# filters_no_gnd_vias.net
KiCad netlist of a schematic drawn in EAGLE
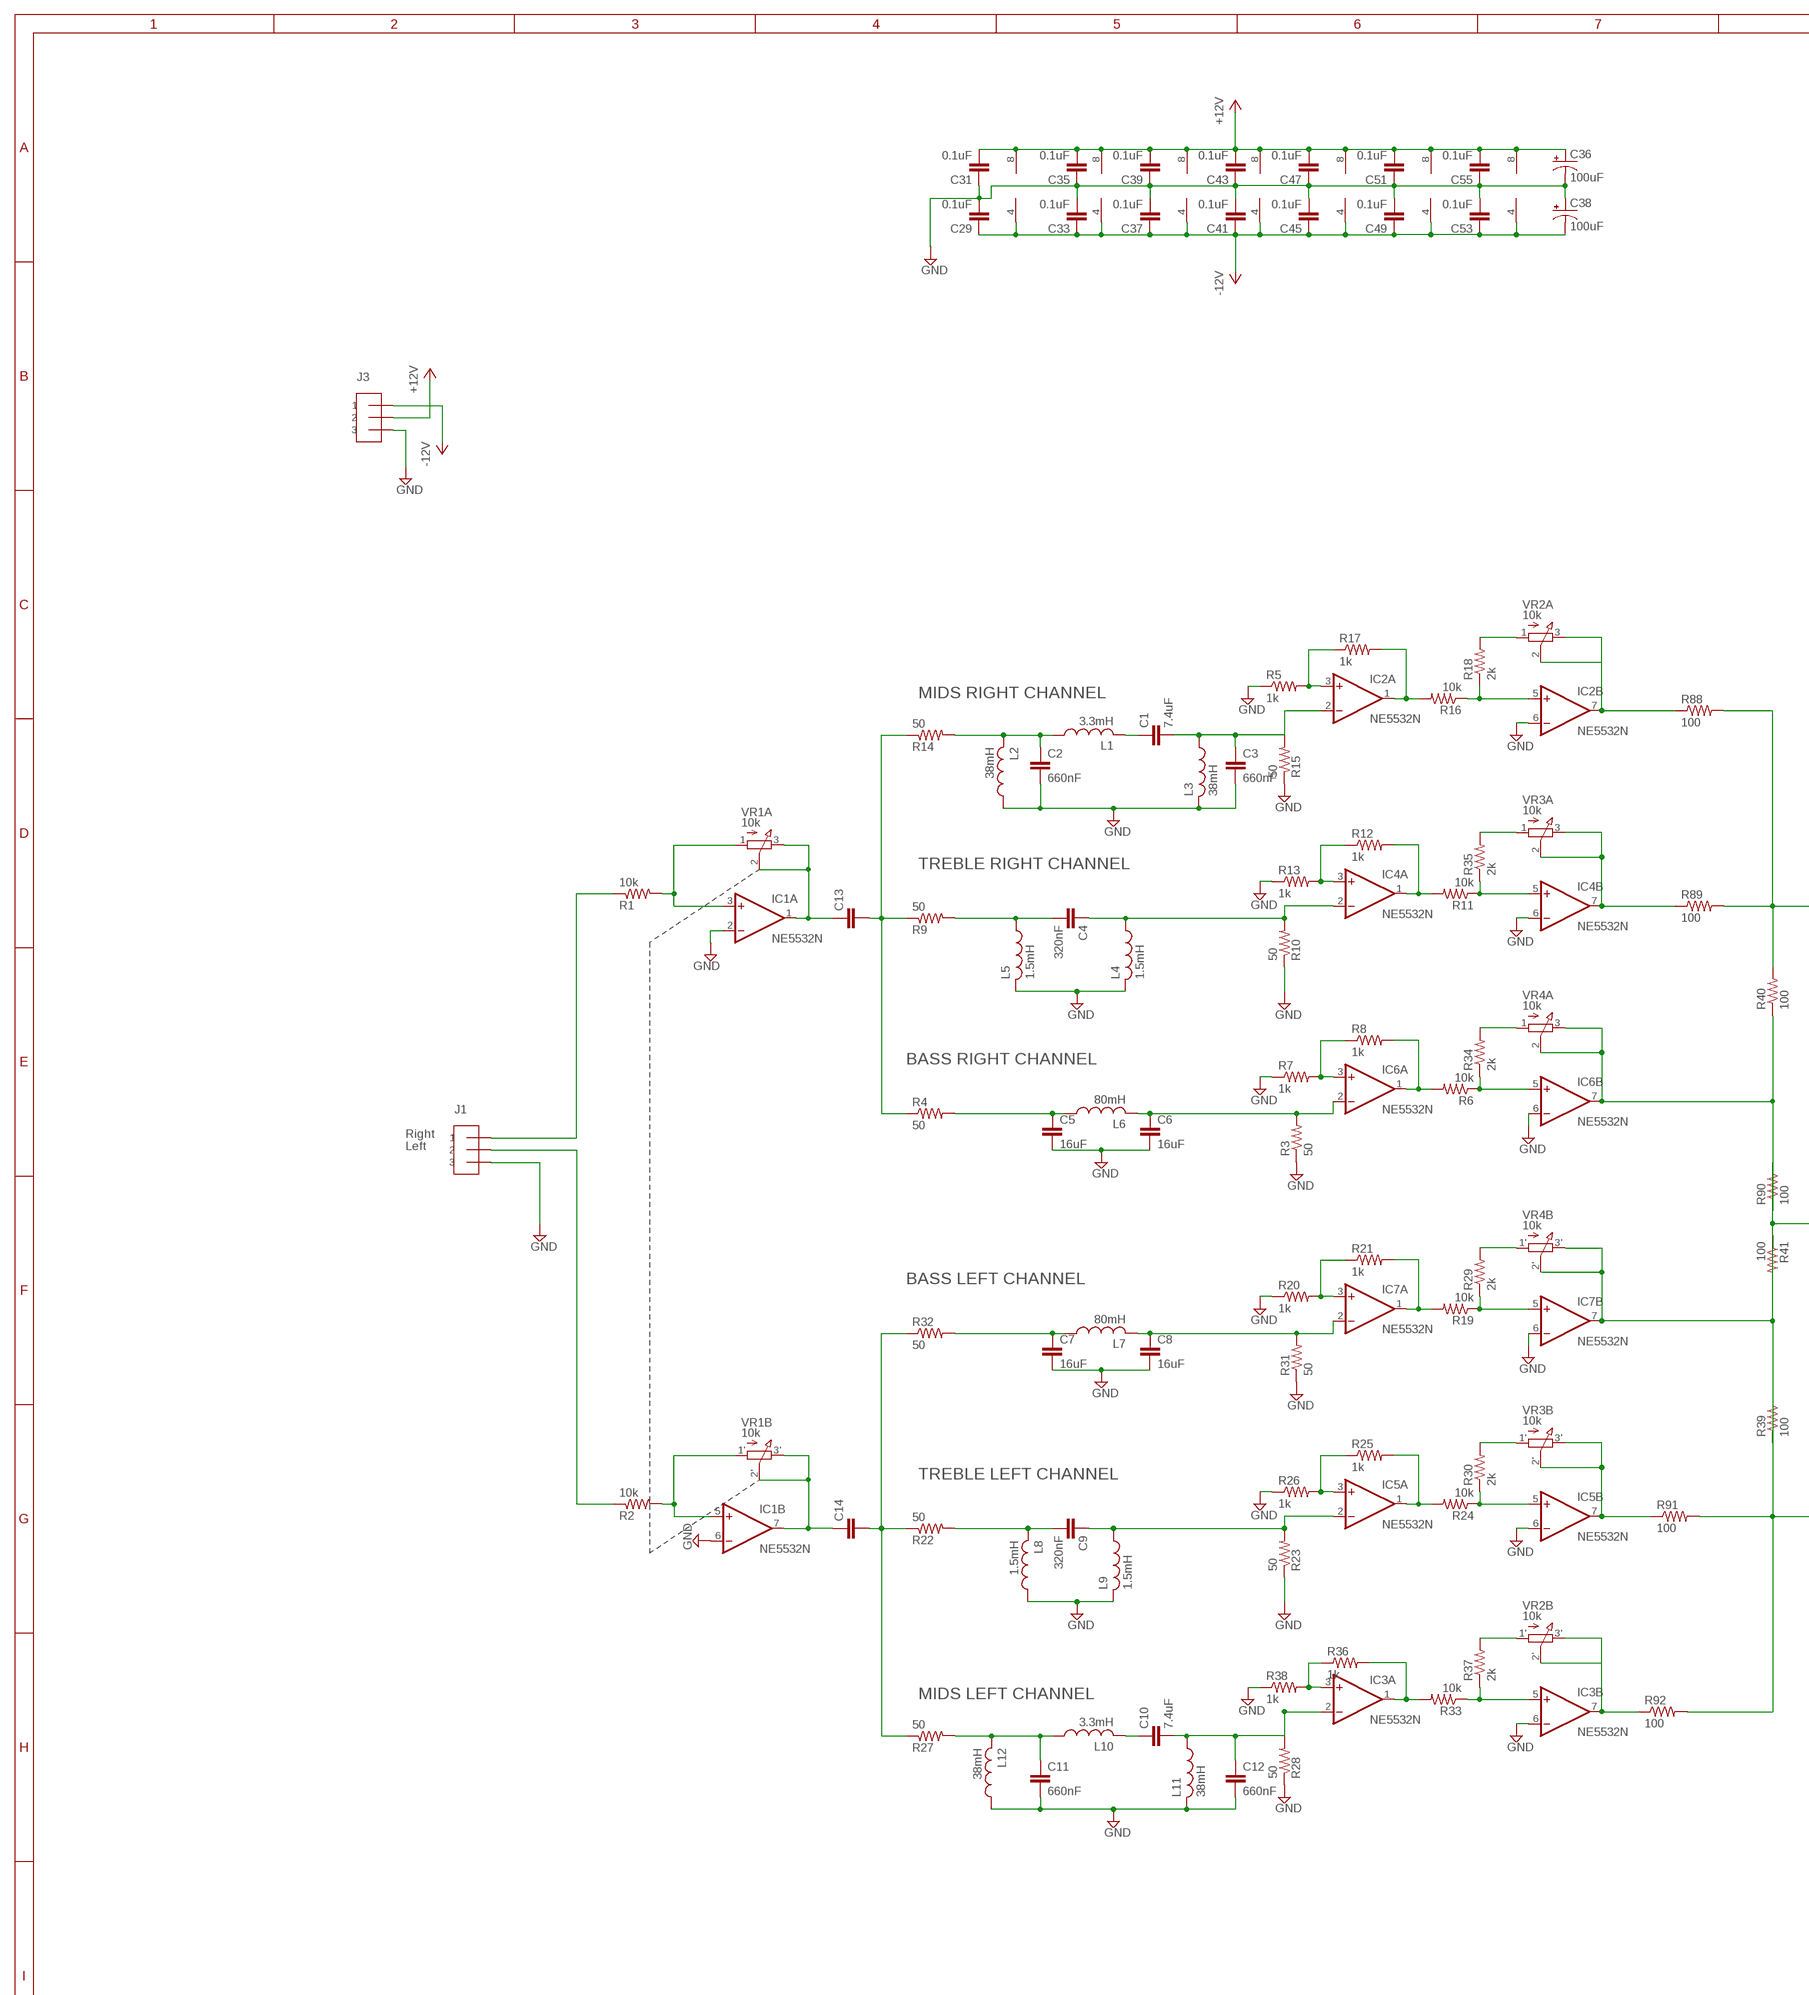
[diagram p0: schematic, sheet 1, part 1 of 2]
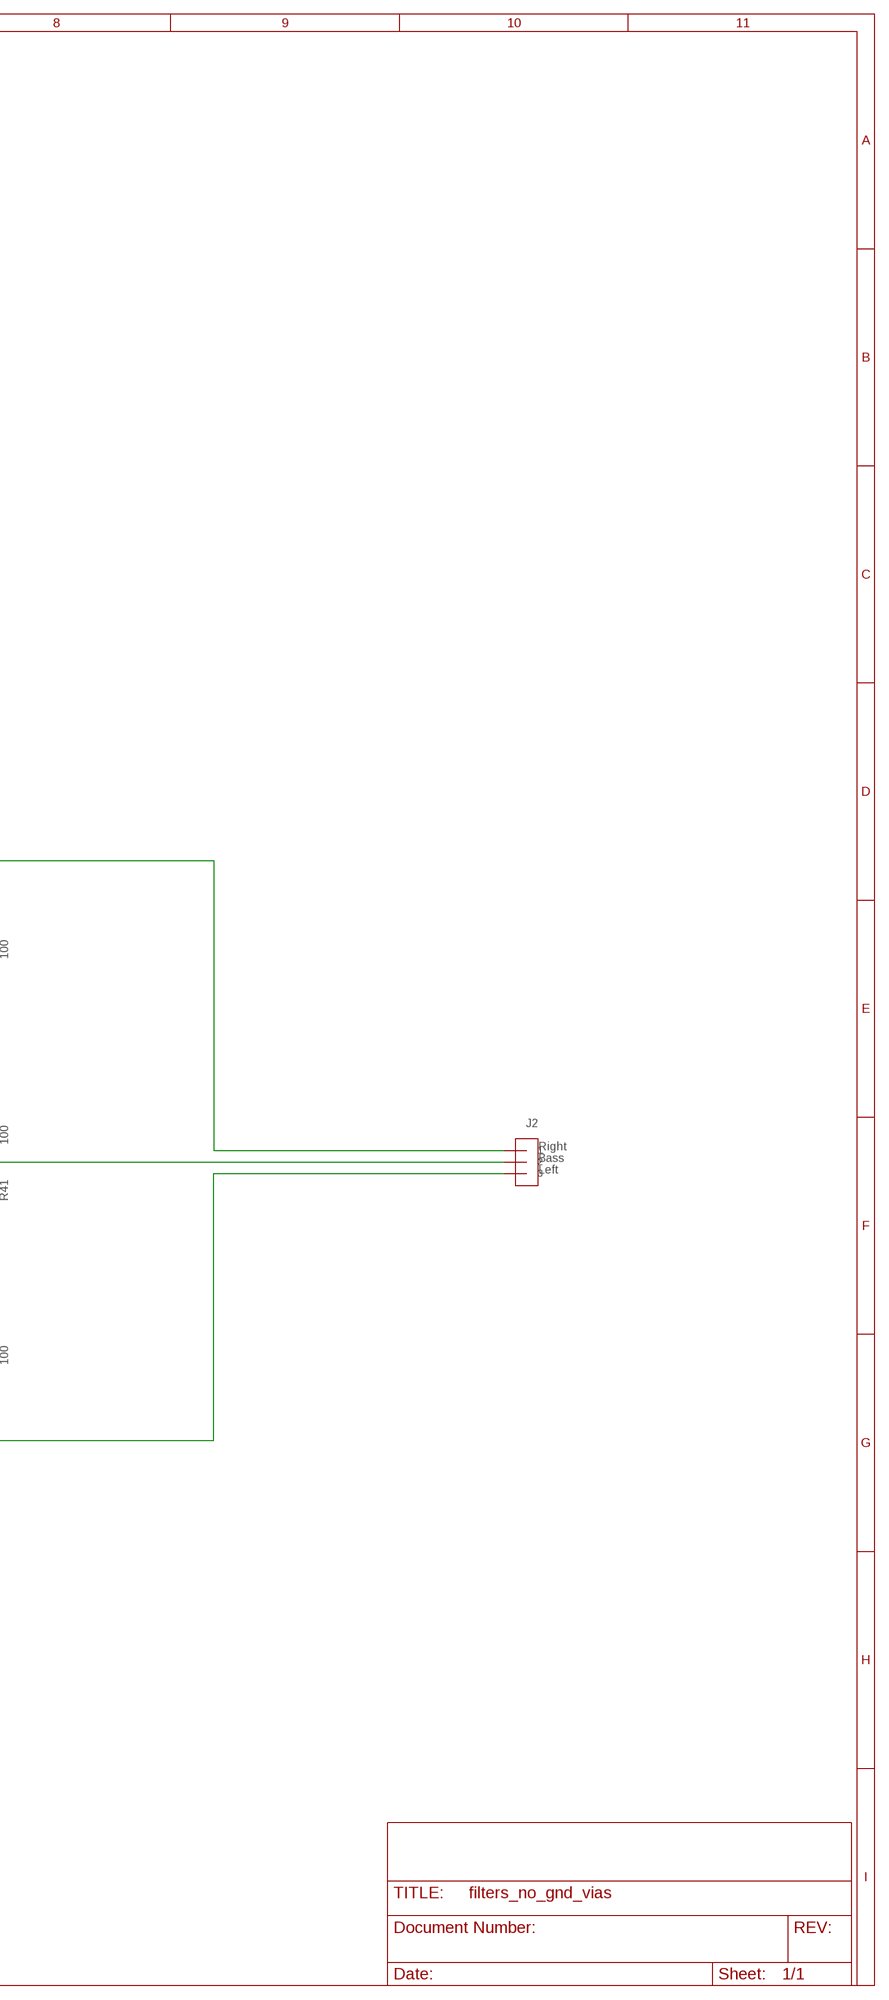
[diagram p1: schematic, sheet 1, part 2 of 2]

(export (version "E")
  (design (tool "Eeschema 10.0.6"))
  (components
    (comp (ref "C1")
      (value "7.4uF")
      (footprint "eagle-import:C025-024X044")
      (libsource (lib "eagle-import") (part "C-EU025-024X044"))
    )
    (comp (ref "C2")
      (value "660nF")
      (footprint "eagle-import:C025-024X044")
      (libsource (lib "eagle-import") (part "C-EU025-024X044"))
    )
    (comp (ref "C3")
      (value "660nF")
      (footprint "eagle-import:C025-024X044")
      (libsource (lib "eagle-import") (part "C-EU025-024X044"))
    )
    (comp (ref "C4")
      (value "320nF")
      (footprint "eagle-import:C025-024X044")
      (libsource (lib "eagle-import") (part "C-EU025-024X044"))
    )
    (comp (ref "C5")
      (value "16uF")
      (footprint "eagle-import:C025-024X044")
      (libsource (lib "eagle-import") (part "C-EU025-024X044"))
    )
    (comp (ref "C6")
      (value "16uF")
      (footprint "eagle-import:C025-024X044")
      (libsource (lib "eagle-import") (part "C-EU025-024X044"))
    )
    (comp (ref "C7")
      (value "16uF")
      (footprint "eagle-import:C025-024X044")
      (libsource (lib "eagle-import") (part "C-EU025-024X044"))
    )
    (comp (ref "C8")
      (value "16uF")
      (footprint "eagle-import:C025-024X044")
      (libsource (lib "eagle-import") (part "C-EU025-024X044"))
    )
    (comp (ref "C9")
      (value "320nF")
      (footprint "eagle-import:C025-024X044")
      (libsource (lib "eagle-import") (part "C-EU025-024X044"))
    )
    (comp (ref "C10")
      (value "7.4uF")
      (footprint "eagle-import:C025-024X044")
      (libsource (lib "eagle-import") (part "C-EU025-024X044"))
    )
    (comp (ref "C11")
      (value "660nF")
      (footprint "eagle-import:C025-024X044")
      (libsource (lib "eagle-import") (part "C-EU025-024X044"))
    )
    (comp (ref "C12")
      (value "660nF")
      (footprint "eagle-import:C025-024X044")
      (libsource (lib "eagle-import") (part "C-EU025-024X044"))
    )
    (comp (ref "C13")
      (value "C-EU025-024X044")
      (footprint "eagle-import:C025-024X044")
      (libsource (lib "eagle-import") (part "C-EU025-024X044"))
    )
    (comp (ref "C14")
      (value "C-EU025-024X044")
      (footprint "eagle-import:C025-024X044")
      (libsource (lib "eagle-import") (part "C-EU025-024X044"))
    )
    (comp (ref "C29")
      (value "0.1uF")
      (footprint "eagle-import:C025-024X044")
      (libsource (lib "eagle-import") (part "C-EU025-024X044"))
    )
    (comp (ref "C31")
      (value "0.1uF")
      (footprint "eagle-import:C025-024X044")
      (libsource (lib "eagle-import") (part "C-EU025-024X044"))
    )
    (comp (ref "C33")
      (value "0.1uF")
      (footprint "eagle-import:C025-024X044")
      (libsource (lib "eagle-import") (part "C-EU025-024X044"))
    )
    (comp (ref "C35")
      (value "0.1uF")
      (footprint "eagle-import:C025-024X044")
      (libsource (lib "eagle-import") (part "C-EU025-024X044"))
    )
    (comp (ref "C36")
      (value "100uF")
      (footprint "eagle-import:E2,5-6")
      (libsource (lib "eagle-import") (part "CPOL-USE2.5-6"))
    )
    (comp (ref "C37")
      (value "0.1uF")
      (footprint "eagle-import:C025-024X044")
      (libsource (lib "eagle-import") (part "C-EU025-024X044"))
    )
    (comp (ref "C38")
      (value "100uF")
      (footprint "eagle-import:E2,5-6")
      (libsource (lib "eagle-import") (part "CPOL-USE2.5-6"))
    )
    (comp (ref "C39")
      (value "0.1uF")
      (footprint "eagle-import:C025-024X044")
      (libsource (lib "eagle-import") (part "C-EU025-024X044"))
    )
    (comp (ref "C41")
      (value "0.1uF")
      (footprint "eagle-import:C025-024X044")
      (libsource (lib "eagle-import") (part "C-EU025-024X044"))
    )
    (comp (ref "C43")
      (value "0.1uF")
      (footprint "eagle-import:C025-024X044")
      (libsource (lib "eagle-import") (part "C-EU025-024X044"))
    )
    (comp (ref "C45")
      (value "0.1uF")
      (footprint "eagle-import:C025-024X044")
      (libsource (lib "eagle-import") (part "C-EU025-024X044"))
    )
    (comp (ref "C47")
      (value "0.1uF")
      (footprint "eagle-import:C025-024X044")
      (libsource (lib "eagle-import") (part "C-EU025-024X044"))
    )
    (comp (ref "C49")
      (value "0.1uF")
      (footprint "eagle-import:C025-024X044")
      (libsource (lib "eagle-import") (part "C-EU025-024X044"))
    )
    (comp (ref "C51")
      (value "0.1uF")
      (footprint "eagle-import:C025-024X044")
      (libsource (lib "eagle-import") (part "C-EU025-024X044"))
    )
    (comp (ref "C53")
      (value "0.1uF")
      (footprint "eagle-import:C025-024X044")
      (libsource (lib "eagle-import") (part "C-EU025-024X044"))
    )
    (comp (ref "C55")
      (value "0.1uF")
      (footprint "eagle-import:C025-024X044")
      (libsource (lib "eagle-import") (part "C-EU025-024X044"))
    )
    (comp (ref "IC1")
      (value "NE5532N")
      (footprint "eagle-import:DIL08")
      (libsource (lib "eagle-import") (part "NE5532N"))
    )
    (comp (ref "IC2")
      (value "NE5532N")
      (footprint "eagle-import:DIL08")
      (libsource (lib "eagle-import") (part "NE5532N"))
    )
    (comp (ref "IC3")
      (value "NE5532N")
      (footprint "eagle-import:DIL08")
      (libsource (lib "eagle-import") (part "NE5532N"))
    )
    (comp (ref "IC4")
      (value "NE5532N")
      (footprint "eagle-import:DIL08")
      (libsource (lib "eagle-import") (part "NE5532N"))
    )
    (comp (ref "IC5")
      (value "NE5532N")
      (footprint "eagle-import:DIL08")
      (libsource (lib "eagle-import") (part "NE5532N"))
    )
    (comp (ref "IC6")
      (value "NE5532N")
      (footprint "eagle-import:DIL08")
      (libsource (lib "eagle-import") (part "NE5532N"))
    )
    (comp (ref "IC7")
      (value "NE5532N")
      (footprint "eagle-import:DIL08")
      (libsource (lib "eagle-import") (part "NE5532N"))
    )
    (comp (ref "J1")
      (value "3_PIN_AMPCONN")
      (footprint "eagle-import:3_PIN_AMPCONN")
      (libsource (lib "eagle-import") (part "3_PIN_AMPCONN"))
    )
    (comp (ref "J2")
      (value "3_PIN_AMPCONN")
      (footprint "eagle-import:3_PIN_AMPCONN")
      (libsource (lib "eagle-import") (part "3_PIN_AMPCONN"))
    )
    (comp (ref "J3")
      (value "3_PIN_AMPCONN")
      (footprint "eagle-import:3_PIN_AMPCONN")
      (libsource (lib "eagle-import") (part "3_PIN_AMPCONN"))
    )
    (comp (ref "L1")
      (value "3.3mH")
      (footprint "eagle-import:6000-XXXX-RC")
      (libsource (lib "eagle-import") (part "L-US6000-XXX-RC"))
    )
    (comp (ref "L2")
      (value "38mH")
      (footprint "eagle-import:6000-XXXX-RC")
      (libsource (lib "eagle-import") (part "L-US6000-XXX-RC"))
    )
    (comp (ref "L3")
      (value "38mH")
      (footprint "eagle-import:6000-XXXX-RC")
      (libsource (lib "eagle-import") (part "L-US6000-XXX-RC"))
    )
    (comp (ref "L4")
      (value "1.5mH")
      (footprint "eagle-import:6000-XXXX-RC")
      (libsource (lib "eagle-import") (part "L-US6000-XXX-RC"))
    )
    (comp (ref "L5")
      (value "1.5mH")
      (footprint "eagle-import:6000-XXXX-RC")
      (libsource (lib "eagle-import") (part "L-US6000-XXX-RC"))
    )
    (comp (ref "L6")
      (value "80mH")
      (footprint "eagle-import:6000-XXXX-RC")
      (libsource (lib "eagle-import") (part "L-US6000-XXX-RC"))
    )
    (comp (ref "L7")
      (value "80mH")
      (footprint "eagle-import:6000-XXXX-RC")
      (libsource (lib "eagle-import") (part "L-US6000-XXX-RC"))
    )
    (comp (ref "L8")
      (value "1.5mH")
      (footprint "eagle-import:6000-XXXX-RC")
      (libsource (lib "eagle-import") (part "L-US6000-XXX-RC"))
    )
    (comp (ref "L9")
      (value "1.5mH")
      (footprint "eagle-import:6000-XXXX-RC")
      (libsource (lib "eagle-import") (part "L-US6000-XXX-RC"))
    )
    (comp (ref "L10")
      (value "3.3mH")
      (footprint "eagle-import:6000-XXXX-RC")
      (libsource (lib "eagle-import") (part "L-US6000-XXX-RC"))
    )
    (comp (ref "L11")
      (value "38mH")
      (footprint "eagle-import:6000-XXXX-RC")
      (libsource (lib "eagle-import") (part "L-US6000-XXX-RC"))
    )
    (comp (ref "L12")
      (value "38mH")
      (footprint "eagle-import:6000-XXXX-RC")
      (libsource (lib "eagle-import") (part "L-US6000-XXX-RC"))
    )
    (comp (ref "R1")
      (value "10k")
      (footprint "eagle-import:0204V")
      (libsource (lib "eagle-import") (part "R-US_0204/2V"))
    )
    (comp (ref "R2")
      (value "10k")
      (footprint "eagle-import:0204V")
      (libsource (lib "eagle-import") (part "R-US_0204/2V"))
    )
    (comp (ref "R3")
      (value "50")
      (footprint "eagle-import:0204V")
      (libsource (lib "eagle-import") (part "R-US_0204/2V"))
    )
    (comp (ref "R4")
      (value "50")
      (footprint "eagle-import:0204V")
      (libsource (lib "eagle-import") (part "R-US_0204/2V"))
    )
    (comp (ref "R5")
      (value "1k")
      (footprint "eagle-import:0204V")
      (libsource (lib "eagle-import") (part "R-US_0204/2V"))
    )
    (comp (ref "R6")
      (value "10k")
      (footprint "eagle-import:0204V")
      (libsource (lib "eagle-import") (part "R-US_0204/2V"))
    )
    (comp (ref "R7")
      (value "1k")
      (footprint "eagle-import:0204V")
      (libsource (lib "eagle-import") (part "R-US_0204/2V"))
    )
    (comp (ref "R8")
      (value "1k")
      (footprint "eagle-import:0204V")
      (libsource (lib "eagle-import") (part "R-US_0204/2V"))
    )
    (comp (ref "R9")
      (value "50")
      (footprint "eagle-import:0204V")
      (libsource (lib "eagle-import") (part "R-US_0204/2V"))
    )
    (comp (ref "R10")
      (value "50")
      (footprint "eagle-import:0204V")
      (libsource (lib "eagle-import") (part "R-US_0204/2V"))
    )
    (comp (ref "R11")
      (value "10k")
      (footprint "eagle-import:0204V")
      (libsource (lib "eagle-import") (part "R-US_0204/2V"))
    )
    (comp (ref "R12")
      (value "1k")
      (footprint "eagle-import:0204V")
      (libsource (lib "eagle-import") (part "R-US_0204/2V"))
    )
    (comp (ref "R13")
      (value "1k")
      (footprint "eagle-import:0204V")
      (libsource (lib "eagle-import") (part "R-US_0204/2V"))
    )
    (comp (ref "R14")
      (value "50")
      (footprint "eagle-import:0204V")
      (libsource (lib "eagle-import") (part "R-US_0204/2V"))
    )
    (comp (ref "R15")
      (value "50")
      (footprint "eagle-import:0204V")
      (libsource (lib "eagle-import") (part "R-US_0204/2V"))
    )
    (comp (ref "R16")
      (value "10k")
      (footprint "eagle-import:0204V")
      (libsource (lib "eagle-import") (part "R-US_0204/2V"))
    )
    (comp (ref "R17")
      (value "1k")
      (footprint "eagle-import:0204V")
      (libsource (lib "eagle-import") (part "R-US_0204/2V"))
    )
    (comp (ref "R18")
      (value "2k")
      (footprint "eagle-import:0204V")
      (libsource (lib "eagle-import") (part "R-US_0204/2V"))
    )
    (comp (ref "R19")
      (value "10k")
      (footprint "eagle-import:0204V")
      (libsource (lib "eagle-import") (part "R-US_0204/2V"))
    )
    (comp (ref "R20")
      (value "1k")
      (footprint "eagle-import:0204V")
      (libsource (lib "eagle-import") (part "R-US_0204/2V"))
    )
    (comp (ref "R21")
      (value "1k")
      (footprint "eagle-import:0204V")
      (libsource (lib "eagle-import") (part "R-US_0204/2V"))
    )
    (comp (ref "R22")
      (value "50")
      (footprint "eagle-import:0204V")
      (libsource (lib "eagle-import") (part "R-US_0204/2V"))
    )
    (comp (ref "R23")
      (value "50")
      (footprint "eagle-import:0204V")
      (libsource (lib "eagle-import") (part "R-US_0204/2V"))
    )
    (comp (ref "R24")
      (value "10k")
      (footprint "eagle-import:0204V")
      (libsource (lib "eagle-import") (part "R-US_0204/2V"))
    )
    (comp (ref "R25")
      (value "1k")
      (footprint "eagle-import:0204V")
      (libsource (lib "eagle-import") (part "R-US_0204/2V"))
    )
    (comp (ref "R26")
      (value "1k")
      (footprint "eagle-import:0204V")
      (libsource (lib "eagle-import") (part "R-US_0204/2V"))
    )
    (comp (ref "R27")
      (value "50")
      (footprint "eagle-import:0204V")
      (libsource (lib "eagle-import") (part "R-US_0204/2V"))
    )
    (comp (ref "R28")
      (value "50")
      (footprint "eagle-import:0204V")
      (libsource (lib "eagle-import") (part "R-US_0204/2V"))
    )
    (comp (ref "R29")
      (value "2k")
      (footprint "eagle-import:0204V")
      (libsource (lib "eagle-import") (part "R-US_0204/2V"))
    )
    (comp (ref "R30")
      (value "2k")
      (footprint "eagle-import:0204V")
      (libsource (lib "eagle-import") (part "R-US_0204/2V"))
    )
    (comp (ref "R31")
      (value "50")
      (footprint "eagle-import:0204V")
      (libsource (lib "eagle-import") (part "R-US_0204/2V"))
    )
    (comp (ref "R32")
      (value "50")
      (footprint "eagle-import:0204V")
      (libsource (lib "eagle-import") (part "R-US_0204/2V"))
    )
    (comp (ref "R33")
      (value "10k")
      (footprint "eagle-import:0204V")
      (libsource (lib "eagle-import") (part "R-US_0204/2V"))
    )
    (comp (ref "R34")
      (value "2k")
      (footprint "eagle-import:0204V")
      (libsource (lib "eagle-import") (part "R-US_0204/2V"))
    )
    (comp (ref "R35")
      (value "2k")
      (footprint "eagle-import:0204V")
      (libsource (lib "eagle-import") (part "R-US_0204/2V"))
    )
    (comp (ref "R36")
      (value "1k")
      (footprint "eagle-import:0204V")
      (libsource (lib "eagle-import") (part "R-US_0204/2V"))
    )
    (comp (ref "R37")
      (value "2k")
      (footprint "eagle-import:0204V")
      (libsource (lib "eagle-import") (part "R-US_0204/2V"))
    )
    (comp (ref "R38")
      (value "1k")
      (footprint "eagle-import:0204V")
      (libsource (lib "eagle-import") (part "R-US_0204/2V"))
    )
    (comp (ref "R39")
      (value "100")
      (footprint "eagle-import:0204V")
      (libsource (lib "eagle-import") (part "R-US_0204/2V"))
    )
    (comp (ref "R40")
      (value "100")
      (footprint "eagle-import:0204V")
      (libsource (lib "eagle-import") (part "R-US_0204/2V"))
    )
    (comp (ref "R41")
      (value "100")
      (footprint "eagle-import:0204V")
      (libsource (lib "eagle-import") (part "R-US_0204/2V"))
    )
    (comp (ref "R88")
      (value "100")
      (footprint "eagle-import:0204V")
      (libsource (lib "eagle-import") (part "R-US_0204/2V"))
    )
    (comp (ref "R89")
      (value "100")
      (footprint "eagle-import:0204V")
      (libsource (lib "eagle-import") (part "R-US_0204/2V"))
    )
    (comp (ref "R90")
      (value "100")
      (footprint "eagle-import:0204V")
      (libsource (lib "eagle-import") (part "R-US_0204/2V"))
    )
    (comp (ref "R91")
      (value "100")
      (footprint "eagle-import:0204V")
      (libsource (lib "eagle-import") (part "R-US_0204/2V"))
    )
    (comp (ref "R92")
      (value "100")
      (footprint "eagle-import:0204V")
      (libsource (lib "eagle-import") (part "R-US_0204/2V"))
    )
    (comp (ref "VR1")
      (value "10k")
      (footprint "eagle-import:VOL_POT_2GANG")
      (libsource (lib "eagle-import") (part "VOL_POT_2GANG"))
    )
    (comp (ref "VR2")
      (value "10k")
      (footprint "eagle-import:TONE_POT_2GANG")
      (libsource (lib "eagle-import") (part "P140KV1-F25BR"))
    )
    (comp (ref "VR3")
      (value "10k")
      (footprint "eagle-import:TONE_POT_2GANG")
      (libsource (lib "eagle-import") (part "P140KV1-F25BR"))
    )
    (comp (ref "VR4")
      (value "10k")
      (footprint "eagle-import:TONE_POT_2GANG")
      (libsource (lib "eagle-import") (part "P140KV1-F25BR"))
    )
  )
  (nets
    (net (code "1") (name "+12V") (class "Default")
      (node (ref "C31") (pin "2") (pinfunction "2_2") (pintype "passive"))
      (node (ref "C35") (pin "2") (pinfunction "2_2") (pintype "passive"))
      (node (ref "C36") (pin "+") (pinfunction "+_+") (pintype "passive"))
      (node (ref "C39") (pin "2") (pinfunction "2_2") (pintype "passive"))
      (node (ref "C43") (pin "2") (pinfunction "2_2") (pintype "passive"))
      (node (ref "C47") (pin "2") (pinfunction "2_2") (pintype "passive"))
      (node (ref "C51") (pin "2") (pinfunction "2_2") (pintype "passive"))
      (node (ref "C55") (pin "2") (pinfunction "2_2") (pintype "passive"))
      (node (ref "IC1") (pin "8") (pinfunction "V+_8") (pintype "power_in"))
      (node (ref "IC2") (pin "8") (pinfunction "V+_8") (pintype "power_in"))
      (node (ref "IC3") (pin "8") (pinfunction "V+_8") (pintype "power_in"))
      (node (ref "IC4") (pin "8") (pinfunction "V+_8") (pintype "power_in"))
      (node (ref "IC5") (pin "8") (pinfunction "V+_8") (pintype "power_in"))
      (node (ref "IC6") (pin "8") (pinfunction "V+_8") (pintype "power_in"))
      (node (ref "IC7") (pin "8") (pinfunction "V+_8") (pintype "power_in"))
      (node (ref "J3") (pin "2") (pinfunction "2_2") (pintype "passive"))
    )
    (net (code "2") (name "-12V") (class "Default")
      (node (ref "C29") (pin "1") (pinfunction "1_1") (pintype "passive"))
      (node (ref "C33") (pin "1") (pinfunction "1_1") (pintype "passive"))
      (node (ref "C37") (pin "1") (pinfunction "1_1") (pintype "passive"))
      (node (ref "C38") (pin "-") (pinfunction "-_-") (pintype "passive"))
      (node (ref "C41") (pin "1") (pinfunction "1_1") (pintype "passive"))
      (node (ref "C45") (pin "1") (pinfunction "1_1") (pintype "passive"))
      (node (ref "C49") (pin "1") (pinfunction "1_1") (pintype "passive"))
      (node (ref "C53") (pin "1") (pinfunction "1_1") (pintype "passive"))
      (node (ref "IC1") (pin "4") (pinfunction "V-_4") (pintype "power_in"))
      (node (ref "IC2") (pin "4") (pinfunction "V-_4") (pintype "power_in"))
      (node (ref "IC3") (pin "4") (pinfunction "V-_4") (pintype "power_in"))
      (node (ref "IC4") (pin "4") (pinfunction "V-_4") (pintype "power_in"))
      (node (ref "IC5") (pin "4") (pinfunction "V-_4") (pintype "power_in"))
      (node (ref "IC6") (pin "4") (pinfunction "V-_4") (pintype "power_in"))
      (node (ref "IC7") (pin "4") (pinfunction "V-_4") (pintype "power_in"))
      (node (ref "J3") (pin "1") (pinfunction "1_1") (pintype "passive"))
    )
    (net (code "3") (name "GND") (class "Default")
      (node (ref "C11") (pin "2") (pinfunction "2_2") (pintype "passive"))
      (node (ref "C12") (pin "2") (pinfunction "2_2") (pintype "passive"))
      (node (ref "C2") (pin "2") (pinfunction "2_2") (pintype "passive"))
      (node (ref "C29") (pin "2") (pinfunction "2_2") (pintype "passive"))
      (node (ref "C3") (pin "2") (pinfunction "2_2") (pintype "passive"))
      (node (ref "C31") (pin "1") (pinfunction "1_1") (pintype "passive"))
      (node (ref "C33") (pin "2") (pinfunction "2_2") (pintype "passive"))
      (node (ref "C35") (pin "1") (pinfunction "1_1") (pintype "passive"))
      (node (ref "C36") (pin "-") (pinfunction "-_-") (pintype "passive"))
      (node (ref "C37") (pin "2") (pinfunction "2_2") (pintype "passive"))
      (node (ref "C38") (pin "+") (pinfunction "+_+") (pintype "passive"))
      (node (ref "C39") (pin "1") (pinfunction "1_1") (pintype "passive"))
      (node (ref "C41") (pin "2") (pinfunction "2_2") (pintype "passive"))
      (node (ref "C43") (pin "1") (pinfunction "1_1") (pintype "passive"))
      (node (ref "C45") (pin "2") (pinfunction "2_2") (pintype "passive"))
      (node (ref "C47") (pin "1") (pinfunction "1_1") (pintype "passive"))
      (node (ref "C49") (pin "2") (pinfunction "2_2") (pintype "passive"))
      (node (ref "C5") (pin "2") (pinfunction "2_2") (pintype "passive"))
      (node (ref "C51") (pin "1") (pinfunction "1_1") (pintype "passive"))
      (node (ref "C53") (pin "2") (pinfunction "2_2") (pintype "passive"))
      (node (ref "C55") (pin "1") (pinfunction "1_1") (pintype "passive"))
      (node (ref "C6") (pin "2") (pinfunction "2_2") (pintype "passive"))
      (node (ref "C7") (pin "2") (pinfunction "2_2") (pintype "passive"))
      (node (ref "C8") (pin "2") (pinfunction "2_2") (pintype "passive"))
      (node (ref "IC1") (pin "2") (pinfunction "-IN_2") (pintype "input"))
      (node (ref "IC1") (pin "6") (pinfunction "-IN_6") (pintype "input"))
      (node (ref "IC2") (pin "6") (pinfunction "-IN_6") (pintype "input"))
      (node (ref "IC3") (pin "6") (pinfunction "-IN_6") (pintype "input"))
      (node (ref "IC4") (pin "6") (pinfunction "-IN_6") (pintype "input"))
      (node (ref "IC5") (pin "6") (pinfunction "-IN_6") (pintype "input"))
      (node (ref "IC6") (pin "6") (pinfunction "-IN_6") (pintype "input"))
      (node (ref "IC7") (pin "6") (pinfunction "-IN_6") (pintype "input"))
      (node (ref "J1") (pin "3") (pinfunction "3_3") (pintype "passive"))
      (node (ref "J3") (pin "3") (pinfunction "3_3") (pintype "passive"))
      (node (ref "L11") (pin "2") (pinfunction "2_2") (pintype "passive"))
      (node (ref "L12") (pin "1") (pinfunction "1_1") (pintype "passive"))
      (node (ref "L2") (pin "1") (pinfunction "1_1") (pintype "passive"))
      (node (ref "L3") (pin "2") (pinfunction "2_2") (pintype "passive"))
      (node (ref "L4") (pin "2") (pinfunction "2_2") (pintype "passive"))
      (node (ref "L5") (pin "2") (pinfunction "2_2") (pintype "passive"))
      (node (ref "L8") (pin "1") (pinfunction "1_1") (pintype "passive"))
      (node (ref "L9") (pin "2") (pinfunction "2_2") (pintype "passive"))
      (node (ref "R10") (pin "1") (pinfunction "1_1") (pintype "passive"))
      (node (ref "R13") (pin "1") (pinfunction "1_1") (pintype "passive"))
      (node (ref "R15") (pin "1") (pinfunction "1_1") (pintype "passive"))
      (node (ref "R20") (pin "1") (pinfunction "1_1") (pintype "passive"))
      (node (ref "R23") (pin "1") (pinfunction "1_1") (pintype "passive"))
      (node (ref "R26") (pin "1") (pinfunction "1_1") (pintype "passive"))
      (node (ref "R28") (pin "1") (pinfunction "1_1") (pintype "passive"))
      (node (ref "R3") (pin "1") (pinfunction "1_1") (pintype "passive"))
      (node (ref "R31") (pin "1") (pinfunction "1_1") (pintype "passive"))
      (node (ref "R38") (pin "1") (pinfunction "1_1") (pintype "passive"))
      (node (ref "R5") (pin "1") (pinfunction "1_1") (pintype "passive"))
      (node (ref "R7") (pin "1") (pinfunction "1_1") (pintype "passive"))
    )
    (net (code "4") (name "Net-(C1-Pad1)") (class "Default")
      (node (ref "C1") (pin "1") (pinfunction "1_1") (pintype "passive"))
      (node (ref "L1") (pin "2") (pinfunction "2_2") (pintype "passive"))
    )
    (net (code "5") (name "Net-(C2-Pad1)") (class "Default")
      (node (ref "C2") (pin "1") (pinfunction "1_1") (pintype "passive"))
      (node (ref "L1") (pin "1") (pinfunction "1_1") (pintype "passive"))
      (node (ref "L2") (pin "2") (pinfunction "2_2") (pintype "passive"))
      (node (ref "R14") (pin "2") (pinfunction "2_2") (pintype "passive"))
    )
    (net (code "6") (name "Net-(C4-Pad2)") (class "Default")
      (node (ref "C4") (pin "2") (pinfunction "2_2") (pintype "passive"))
      (node (ref "L5") (pin "1") (pinfunction "1_1") (pintype "passive"))
      (node (ref "R9") (pin "2") (pinfunction "2_2") (pintype "passive"))
    )
    (net (code "7") (name "Net-(C5-Pad1)") (class "Default")
      (node (ref "C5") (pin "1") (pinfunction "1_1") (pintype "passive"))
      (node (ref "L6") (pin "1") (pinfunction "1_1") (pintype "passive"))
      (node (ref "R4") (pin "2") (pinfunction "2_2") (pintype "passive"))
    )
    (net (code "8") (name "Net-(C7-Pad1)") (class "Default")
      (node (ref "C7") (pin "1") (pinfunction "1_1") (pintype "passive"))
      (node (ref "L7") (pin "1") (pinfunction "1_1") (pintype "passive"))
      (node (ref "R32") (pin "2") (pinfunction "2_2") (pintype "passive"))
    )
    (net (code "9") (name "Net-(C9-Pad2)") (class "Default")
      (node (ref "C9") (pin "2") (pinfunction "2_2") (pintype "passive"))
      (node (ref "L8") (pin "2") (pinfunction "2_2") (pintype "passive"))
      (node (ref "R22") (pin "2") (pinfunction "2_2") (pintype "passive"))
    )
    (net (code "10") (name "Net-(C10-Pad1)") (class "Default")
      (node (ref "C10") (pin "1") (pinfunction "1_1") (pintype "passive"))
      (node (ref "L10") (pin "2") (pinfunction "2_2") (pintype "passive"))
    )
    (net (code "11") (name "Net-(C11-Pad1)") (class "Default")
      (node (ref "C11") (pin "1") (pinfunction "1_1") (pintype "passive"))
      (node (ref "L10") (pin "1") (pinfunction "1_1") (pintype "passive"))
      (node (ref "L12") (pin "2") (pinfunction "2_2") (pintype "passive"))
      (node (ref "R27") (pin "2") (pinfunction "2_2") (pintype "passive"))
    )
    (net (code "12") (name "Net-(C13-Pad2)") (class "Default")
      (node (ref "C13") (pin "2") (pinfunction "2_2") (pintype "passive"))
      (node (ref "R14") (pin "1") (pinfunction "1_1") (pintype "passive"))
      (node (ref "R4") (pin "1") (pinfunction "1_1") (pintype "passive"))
      (node (ref "R9") (pin "1") (pinfunction "1_1") (pintype "passive"))
    )
    (net (code "13") (name "Net-(C14-Pad2)") (class "Default")
      (node (ref "C14") (pin "2") (pinfunction "2_2") (pintype "passive"))
      (node (ref "R22") (pin "1") (pinfunction "1_1") (pintype "passive"))
      (node (ref "R27") (pin "1") (pinfunction "1_1") (pintype "passive"))
      (node (ref "R32") (pin "1") (pinfunction "1_1") (pintype "passive"))
    )
    (net (code "14") (name "Net-(IC1A-+IN)") (class "Default")
      (node (ref "IC1") (pin "3") (pinfunction "+IN_3") (pintype "input"))
      (node (ref "R1") (pin "2") (pinfunction "2_2") (pintype "passive"))
      (node (ref "VR1") (pin "1") (pinfunction "1_1") (pintype "passive"))
    )
    (net (code "15") (name "Net-(IC1A-OUT)") (class "Default")
      (node (ref "C13") (pin "1") (pinfunction "1_1") (pintype "passive"))
      (node (ref "IC1") (pin "1") (pinfunction "OUT_1") (pintype "output"))
      (node (ref "VR1") (pin "2") (pinfunction "2_2") (pintype "passive"))
      (node (ref "VR1") (pin "3") (pinfunction "3_3") (pintype "passive"))
    )
    (net (code "16") (name "Net-(IC1B-+IN)") (class "Default")
      (node (ref "IC1") (pin "5") (pinfunction "+IN_5") (pintype "input"))
      (node (ref "R2") (pin "2") (pinfunction "2_2") (pintype "passive"))
      (node (ref "VR1") (pin "1'") (pinfunction "1_1'") (pintype "passive"))
    )
    (net (code "17") (name "Net-(IC1B-OUT)") (class "Default")
      (node (ref "C14") (pin "1") (pinfunction "1_1") (pintype "passive"))
      (node (ref "IC1") (pin "7") (pinfunction "OUT_7") (pintype "output"))
      (node (ref "VR1") (pin "2'") (pinfunction "2_2'") (pintype "passive"))
      (node (ref "VR1") (pin "3'") (pinfunction "3_3'") (pintype "passive"))
    )
    (net (code "18") (name "Net-(IC2A-+IN)") (class "Default")
      (node (ref "IC2") (pin "3") (pinfunction "+IN_3") (pintype "input"))
      (node (ref "R17") (pin "1") (pinfunction "1_1") (pintype "passive"))
      (node (ref "R5") (pin "2") (pinfunction "2_2") (pintype "passive"))
    )
    (net (code "19") (name "Net-(IC2A--IN)") (class "Default")
      (node (ref "C1") (pin "2") (pinfunction "2_2") (pintype "passive"))
      (node (ref "C3") (pin "1") (pinfunction "1_1") (pintype "passive"))
      (node (ref "IC2") (pin "2") (pinfunction "-IN_2") (pintype "input"))
      (node (ref "L3") (pin "1") (pinfunction "1_1") (pintype "passive"))
      (node (ref "R15") (pin "2") (pinfunction "2_2") (pintype "passive"))
    )
    (net (code "20") (name "Net-(IC2A-OUT)") (class "Default")
      (node (ref "IC2") (pin "1") (pinfunction "OUT_1") (pintype "output"))
      (node (ref "R16") (pin "2") (pinfunction "2_2") (pintype "passive"))
      (node (ref "R17") (pin "2") (pinfunction "2_2") (pintype "passive"))
    )
    (net (code "21") (name "Net-(IC2B-+IN)") (class "Default")
      (node (ref "IC2") (pin "5") (pinfunction "+IN_5") (pintype "input"))
      (node (ref "R16") (pin "1") (pinfunction "1_1") (pintype "passive"))
      (node (ref "R18") (pin "1") (pinfunction "1_1") (pintype "passive"))
    )
    (net (code "22") (name "Net-(IC2B-OUT)") (class "Default")
      (node (ref "IC2") (pin "7") (pinfunction "OUT_7") (pintype "output"))
      (node (ref "R88") (pin "1") (pinfunction "1_1") (pintype "passive"))
      (node (ref "VR2") (pin "2") (pinfunction "1_2_2") (pintype "passive"))
      (node (ref "VR2") (pin "3") (pinfunction "1_3_3") (pintype "passive"))
    )
    (net (code "23") (name "Net-(IC3A-+IN)") (class "Default")
      (node (ref "IC3") (pin "3") (pinfunction "+IN_3") (pintype "input"))
      (node (ref "R36") (pin "1") (pinfunction "1_1") (pintype "passive"))
      (node (ref "R38") (pin "2") (pinfunction "2_2") (pintype "passive"))
    )
    (net (code "24") (name "Net-(IC3A--IN)") (class "Default")
      (node (ref "C10") (pin "2") (pinfunction "2_2") (pintype "passive"))
      (node (ref "C12") (pin "1") (pinfunction "1_1") (pintype "passive"))
      (node (ref "IC3") (pin "2") (pinfunction "-IN_2") (pintype "input"))
      (node (ref "L11") (pin "1") (pinfunction "1_1") (pintype "passive"))
      (node (ref "R28") (pin "2") (pinfunction "2_2") (pintype "passive"))
    )
    (net (code "25") (name "Net-(IC3A-OUT)") (class "Default")
      (node (ref "IC3") (pin "1") (pinfunction "OUT_1") (pintype "output"))
      (node (ref "R33") (pin "2") (pinfunction "2_2") (pintype "passive"))
      (node (ref "R36") (pin "2") (pinfunction "2_2") (pintype "passive"))
    )
    (net (code "26") (name "Net-(IC3B-+IN)") (class "Default")
      (node (ref "IC3") (pin "5") (pinfunction "+IN_5") (pintype "input"))
      (node (ref "R33") (pin "1") (pinfunction "1_1") (pintype "passive"))
      (node (ref "R37") (pin "1") (pinfunction "1_1") (pintype "passive"))
    )
    (net (code "27") (name "Net-(IC3B-OUT)") (class "Default")
      (node (ref "IC3") (pin "7") (pinfunction "OUT_7") (pintype "output"))
      (node (ref "R92") (pin "1") (pinfunction "1_1") (pintype "passive"))
      (node (ref "VR2") (pin "2'") (pinfunction "1_2_2'") (pintype "passive"))
      (node (ref "VR2") (pin "3'") (pinfunction "1_3_3'") (pintype "passive"))
    )
    (net (code "28") (name "Net-(IC4A-+IN)") (class "Default")
      (node (ref "IC4") (pin "3") (pinfunction "+IN_3") (pintype "input"))
      (node (ref "R12") (pin "1") (pinfunction "1_1") (pintype "passive"))
      (node (ref "R13") (pin "2") (pinfunction "2_2") (pintype "passive"))
    )
    (net (code "29") (name "Net-(IC4A--IN)") (class "Default")
      (node (ref "C4") (pin "1") (pinfunction "1_1") (pintype "passive"))
      (node (ref "IC4") (pin "2") (pinfunction "-IN_2") (pintype "input"))
      (node (ref "L4") (pin "1") (pinfunction "1_1") (pintype "passive"))
      (node (ref "R10") (pin "2") (pinfunction "2_2") (pintype "passive"))
    )
    (net (code "30") (name "Net-(IC4A-OUT)") (class "Default")
      (node (ref "IC4") (pin "1") (pinfunction "OUT_1") (pintype "output"))
      (node (ref "R11") (pin "2") (pinfunction "2_2") (pintype "passive"))
      (node (ref "R12") (pin "2") (pinfunction "2_2") (pintype "passive"))
    )
    (net (code "31") (name "Net-(IC4B-+IN)") (class "Default")
      (node (ref "IC4") (pin "5") (pinfunction "+IN_5") (pintype "input"))
      (node (ref "R11") (pin "1") (pinfunction "1_1") (pintype "passive"))
      (node (ref "R35") (pin "1") (pinfunction "1_1") (pintype "passive"))
    )
    (net (code "32") (name "Net-(IC4B-OUT)") (class "Default")
      (node (ref "IC4") (pin "7") (pinfunction "OUT_7") (pintype "output"))
      (node (ref "R89") (pin "1") (pinfunction "1_1") (pintype "passive"))
      (node (ref "VR3") (pin "2") (pinfunction "1_2_2") (pintype "passive"))
      (node (ref "VR3") (pin "3") (pinfunction "1_3_3") (pintype "passive"))
    )
    (net (code "33") (name "Net-(IC5A-+IN)") (class "Default")
      (node (ref "IC5") (pin "3") (pinfunction "+IN_3") (pintype "input"))
      (node (ref "R25") (pin "1") (pinfunction "1_1") (pintype "passive"))
      (node (ref "R26") (pin "2") (pinfunction "2_2") (pintype "passive"))
    )
    (net (code "34") (name "Net-(IC5A--IN)") (class "Default")
      (node (ref "C9") (pin "1") (pinfunction "1_1") (pintype "passive"))
      (node (ref "IC5") (pin "2") (pinfunction "-IN_2") (pintype "input"))
      (node (ref "L9") (pin "1") (pinfunction "1_1") (pintype "passive"))
      (node (ref "R23") (pin "2") (pinfunction "2_2") (pintype "passive"))
    )
    (net (code "35") (name "Net-(IC5A-OUT)") (class "Default")
      (node (ref "IC5") (pin "1") (pinfunction "OUT_1") (pintype "output"))
      (node (ref "R24") (pin "2") (pinfunction "2_2") (pintype "passive"))
      (node (ref "R25") (pin "2") (pinfunction "2_2") (pintype "passive"))
    )
    (net (code "36") (name "Net-(IC5B-+IN)") (class "Default")
      (node (ref "IC5") (pin "5") (pinfunction "+IN_5") (pintype "input"))
      (node (ref "R24") (pin "1") (pinfunction "1_1") (pintype "passive"))
      (node (ref "R30") (pin "1") (pinfunction "1_1") (pintype "passive"))
    )
    (net (code "37") (name "Net-(IC5B-OUT)") (class "Default")
      (node (ref "IC5") (pin "7") (pinfunction "OUT_7") (pintype "output"))
      (node (ref "R91") (pin "1") (pinfunction "1_1") (pintype "passive"))
      (node (ref "VR3") (pin "2'") (pinfunction "1_2_2'") (pintype "passive"))
      (node (ref "VR3") (pin "3'") (pinfunction "1_3_3'") (pintype "passive"))
    )
    (net (code "38") (name "Net-(IC6A-+IN)") (class "Default")
      (node (ref "IC6") (pin "3") (pinfunction "+IN_3") (pintype "input"))
      (node (ref "R7") (pin "2") (pinfunction "2_2") (pintype "passive"))
      (node (ref "R8") (pin "1") (pinfunction "1_1") (pintype "passive"))
    )
    (net (code "39") (name "Net-(IC6A--IN)") (class "Default")
      (node (ref "C6") (pin "1") (pinfunction "1_1") (pintype "passive"))
      (node (ref "IC6") (pin "2") (pinfunction "-IN_2") (pintype "input"))
      (node (ref "L6") (pin "2") (pinfunction "2_2") (pintype "passive"))
      (node (ref "R3") (pin "2") (pinfunction "2_2") (pintype "passive"))
    )
    (net (code "40") (name "Net-(IC6A-OUT)") (class "Default")
      (node (ref "IC6") (pin "1") (pinfunction "OUT_1") (pintype "output"))
      (node (ref "R6") (pin "2") (pinfunction "2_2") (pintype "passive"))
      (node (ref "R8") (pin "2") (pinfunction "2_2") (pintype "passive"))
    )
    (net (code "41") (name "Net-(IC6B-+IN)") (class "Default")
      (node (ref "IC6") (pin "5") (pinfunction "+IN_5") (pintype "input"))
      (node (ref "R34") (pin "1") (pinfunction "1_1") (pintype "passive"))
      (node (ref "R6") (pin "1") (pinfunction "1_1") (pintype "passive"))
    )
    (net (code "42") (name "Net-(IC6B-OUT)") (class "Default")
      (node (ref "IC6") (pin "7") (pinfunction "OUT_7") (pintype "output"))
      (node (ref "R40") (pin "1") (pinfunction "1_1") (pintype "passive"))
      (node (ref "R90") (pin "1") (pinfunction "1_1") (pintype "passive"))
      (node (ref "VR4") (pin "2") (pinfunction "1_2_2") (pintype "passive"))
      (node (ref "VR4") (pin "3") (pinfunction "1_3_3") (pintype "passive"))
    )
    (net (code "43") (name "Net-(IC7A-+IN)") (class "Default")
      (node (ref "IC7") (pin "3") (pinfunction "+IN_3") (pintype "input"))
      (node (ref "R20") (pin "2") (pinfunction "2_2") (pintype "passive"))
      (node (ref "R21") (pin "1") (pinfunction "1_1") (pintype "passive"))
    )
    (net (code "44") (name "Net-(IC7A--IN)") (class "Default")
      (node (ref "C8") (pin "1") (pinfunction "1_1") (pintype "passive"))
      (node (ref "IC7") (pin "2") (pinfunction "-IN_2") (pintype "input"))
      (node (ref "L7") (pin "2") (pinfunction "2_2") (pintype "passive"))
      (node (ref "R31") (pin "2") (pinfunction "2_2") (pintype "passive"))
    )
    (net (code "45") (name "Net-(IC7A-OUT)") (class "Default")
      (node (ref "IC7") (pin "1") (pinfunction "OUT_1") (pintype "output"))
      (node (ref "R19") (pin "2") (pinfunction "2_2") (pintype "passive"))
      (node (ref "R21") (pin "2") (pinfunction "2_2") (pintype "passive"))
    )
    (net (code "46") (name "Net-(IC7B-+IN)") (class "Default")
      (node (ref "IC7") (pin "5") (pinfunction "+IN_5") (pintype "input"))
      (node (ref "R19") (pin "1") (pinfunction "1_1") (pintype "passive"))
      (node (ref "R29") (pin "1") (pinfunction "1_1") (pintype "passive"))
    )
    (net (code "47") (name "Net-(IC7B-OUT)") (class "Default")
      (node (ref "IC7") (pin "7") (pinfunction "OUT_7") (pintype "output"))
      (node (ref "R39") (pin "1") (pinfunction "1_1") (pintype "passive"))
      (node (ref "R41") (pin "1") (pinfunction "1_1") (pintype "passive"))
      (node (ref "VR4") (pin "2'") (pinfunction "1_2_2'") (pintype "passive"))
      (node (ref "VR4") (pin "3'") (pinfunction "1_3_3'") (pintype "passive"))
    )
    (net (code "48") (name "Net-(J1-Pad1)") (class "Default")
      (node (ref "J1") (pin "1") (pinfunction "1_1") (pintype "passive"))
      (node (ref "R1") (pin "1") (pinfunction "1_1") (pintype "passive"))
    )
    (net (code "49") (name "Net-(J1-Pad2)") (class "Default")
      (node (ref "J1") (pin "2") (pinfunction "2_2") (pintype "passive"))
      (node (ref "R2") (pin "1") (pinfunction "1_1") (pintype "passive"))
    )
    (net (code "50") (name "Net-(J2-Pad1)") (class "Default")
      (node (ref "J2") (pin "1") (pinfunction "1_1") (pintype "passive"))
      (node (ref "R40") (pin "2") (pinfunction "2_2") (pintype "passive"))
      (node (ref "R88") (pin "2") (pinfunction "2_2") (pintype "passive"))
      (node (ref "R89") (pin "2") (pinfunction "2_2") (pintype "passive"))
    )
    (net (code "51") (name "Net-(J2-Pad2)") (class "Default")
      (node (ref "J2") (pin "2") (pinfunction "2_2") (pintype "passive"))
      (node (ref "R41") (pin "2") (pinfunction "2_2") (pintype "passive"))
      (node (ref "R90") (pin "2") (pinfunction "2_2") (pintype "passive"))
    )
    (net (code "52") (name "Net-(J2-Pad3)") (class "Default")
      (node (ref "J2") (pin "3") (pinfunction "3_3") (pintype "passive"))
      (node (ref "R39") (pin "2") (pinfunction "2_2") (pintype "passive"))
      (node (ref "R91") (pin "2") (pinfunction "2_2") (pintype "passive"))
      (node (ref "R92") (pin "2") (pinfunction "2_2") (pintype "passive"))
    )
    (net (code "53") (name "Net-(VR2A-1_1)") (class "Default")
      (node (ref "R18") (pin "2") (pinfunction "2_2") (pintype "passive"))
      (node (ref "VR2") (pin "1") (pinfunction "1_1_1") (pintype "passive"))
    )
    (net (code "54") (name "Net-(VR2B-1_1)") (class "Default")
      (node (ref "R37") (pin "2") (pinfunction "2_2") (pintype "passive"))
      (node (ref "VR2") (pin "1'") (pinfunction "1_1_1'") (pintype "passive"))
    )
    (net (code "55") (name "Net-(VR3A-1_1)") (class "Default")
      (node (ref "R35") (pin "2") (pinfunction "2_2") (pintype "passive"))
      (node (ref "VR3") (pin "1") (pinfunction "1_1_1") (pintype "passive"))
    )
    (net (code "56") (name "Net-(VR3B-1_1)") (class "Default")
      (node (ref "R30") (pin "2") (pinfunction "2_2") (pintype "passive"))
      (node (ref "VR3") (pin "1'") (pinfunction "1_1_1'") (pintype "passive"))
    )
    (net (code "57") (name "Net-(VR4A-1_1)") (class "Default")
      (node (ref "R34") (pin "2") (pinfunction "2_2") (pintype "passive"))
      (node (ref "VR4") (pin "1") (pinfunction "1_1_1") (pintype "passive"))
    )
    (net (code "58") (name "Net-(VR4B-1_1)") (class "Default")
      (node (ref "R29") (pin "2") (pinfunction "2_2") (pintype "passive"))
      (node (ref "VR4") (pin "1'") (pinfunction "1_1_1'") (pintype "passive"))
    )
  )
)
